# XC6SLX09-2FTG256C.net
KiCad netlist of a schematic drawn in Altium Designer
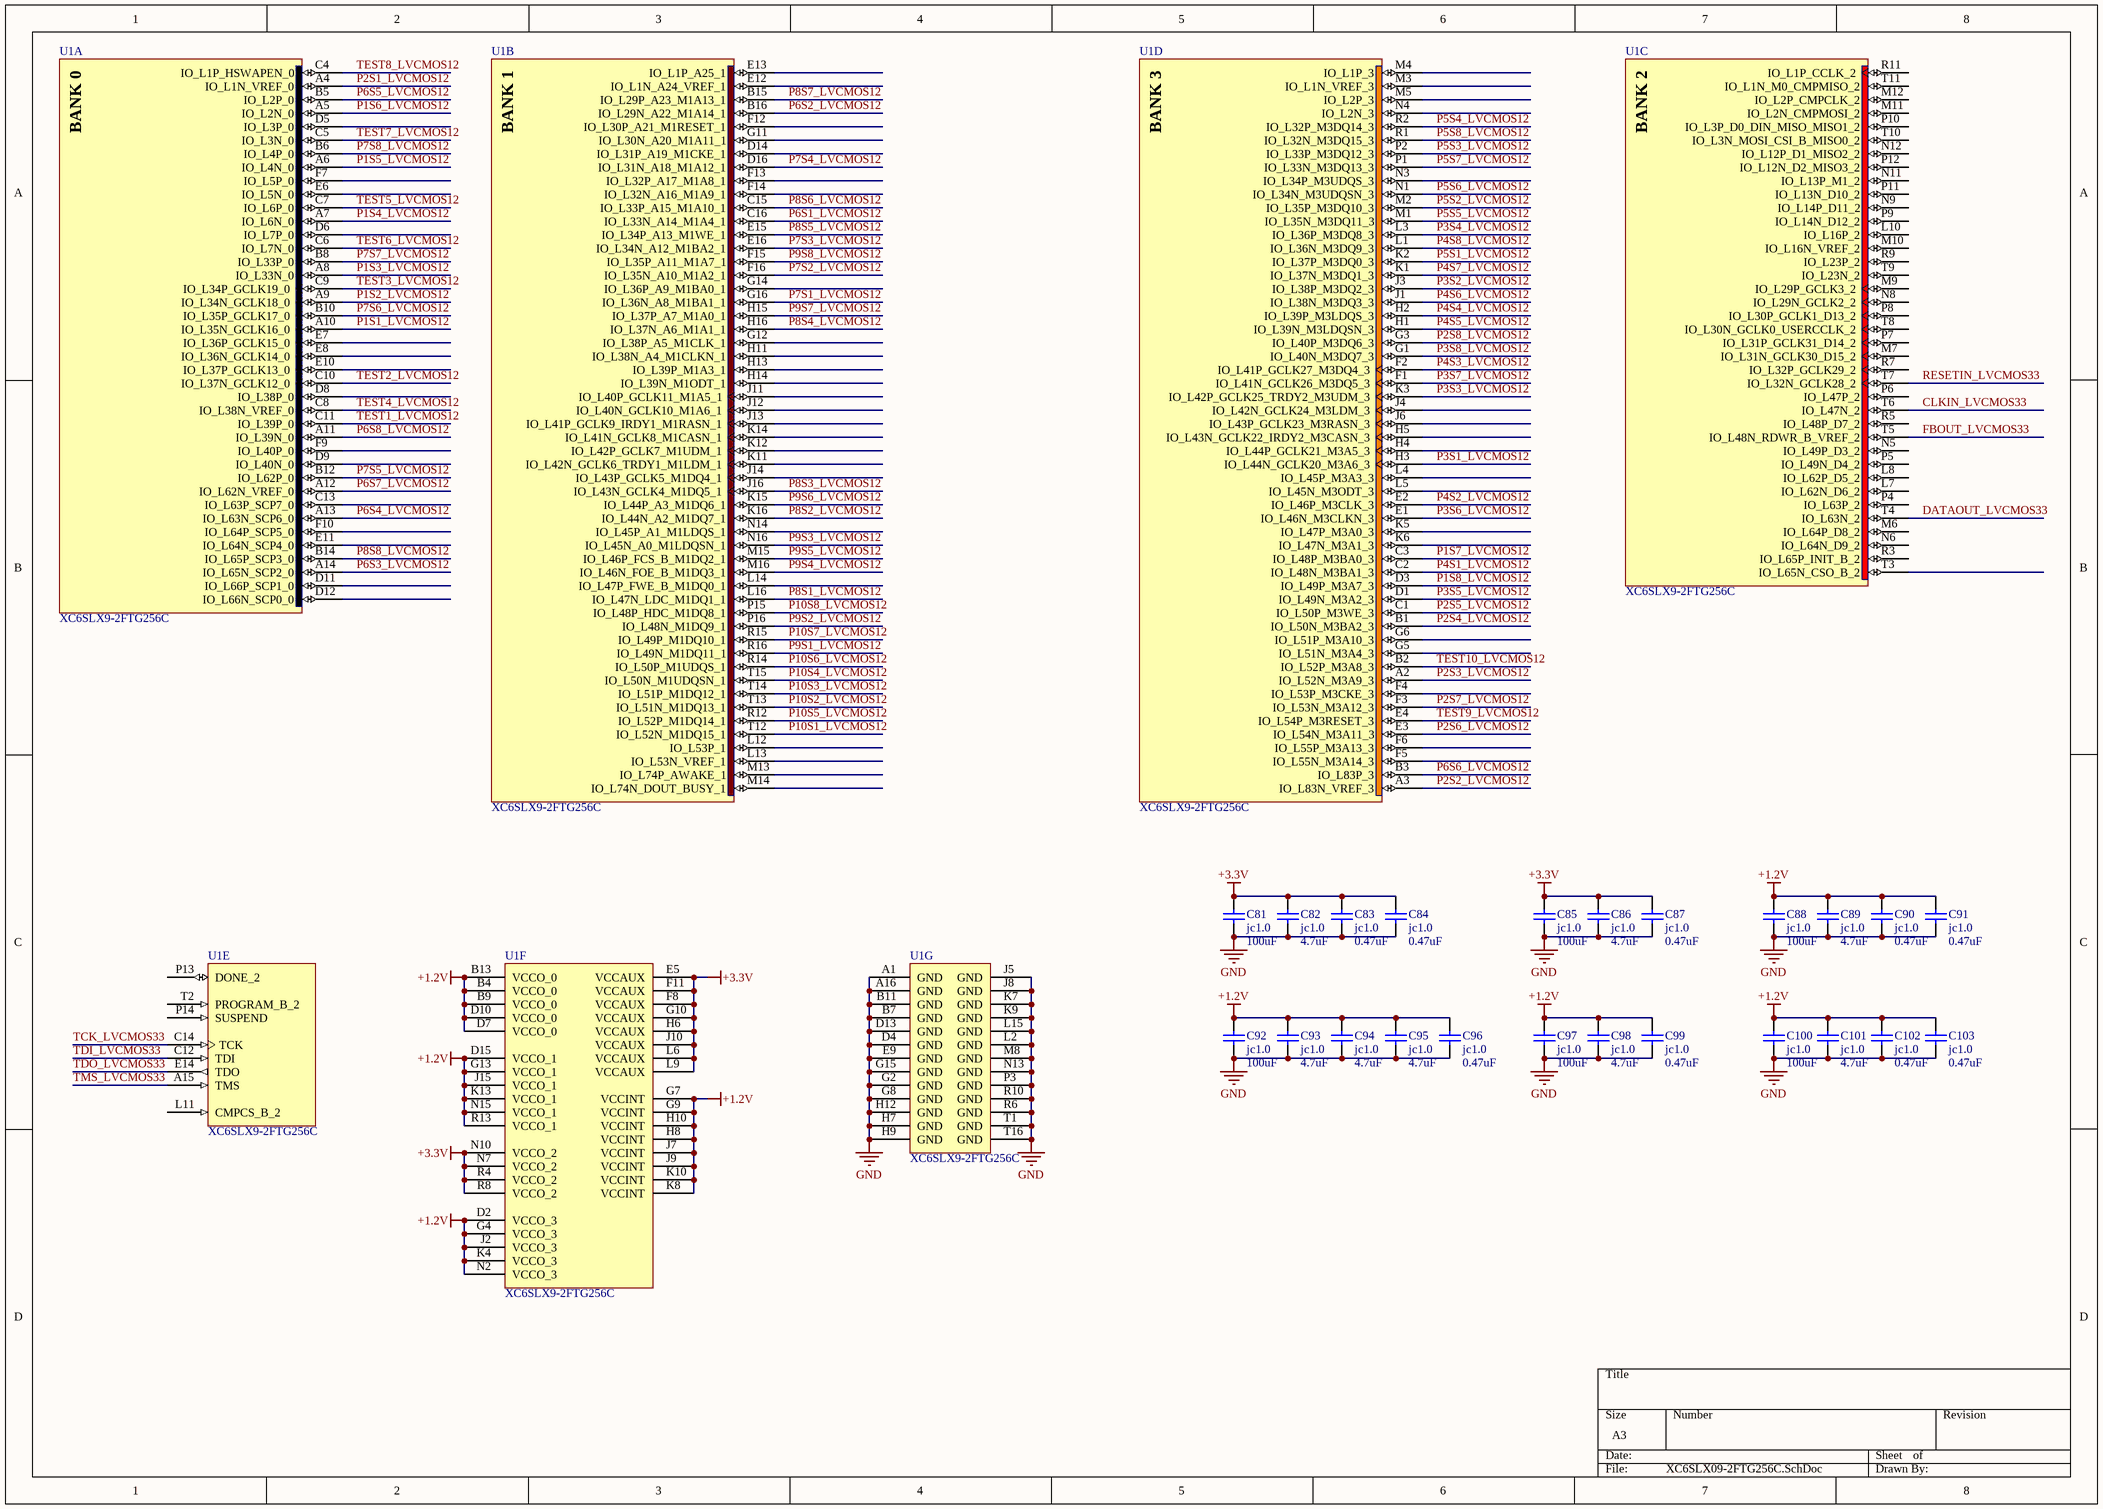
[diagram p0: XC6SLX09-2FTG256C.SchDoc]

(export (version "E")
  (design (tool "Eeschema 10.0.6"))
  (components
    (comp (ref "C81")
      (value "jc1.0")
      (footprint "0805")
      (description "Capacitor")
      (fields (field (name "ALTIUM_VALUE") "100uF") (field (name "PUBLISHER") "Altium Limited"))
      (libsource (lib "LIB01DXP2006SchLib") (part "Cap"))
    )
    (comp (ref "C82")
      (value "jc1.0")
      (footprint "0402")
      (description "Capacitor")
      (fields (field (name "ALTIUM_VALUE") "4.7uF") (field (name "PUBLISHER") "Altium Limited"))
      (libsource (lib "LIB01DXP2006SchLib") (part "Cap"))
    )
    (comp (ref "C83")
      (value "jc1.0")
      (footprint "0402")
      (description "Capacitor")
      (fields (field (name "ALTIUM_VALUE") "0.47uF") (field (name "PUBLISHER") "Altium Limited"))
      (libsource (lib "LIB01DXP2006SchLib") (part "Cap"))
    )
    (comp (ref "C84")
      (value "jc1.0")
      (footprint "0402")
      (description "Capacitor")
      (fields (field (name "ALTIUM_VALUE") "0.47uF") (field (name "PUBLISHER") "Altium Limited"))
      (libsource (lib "LIB01DXP2006SchLib") (part "Cap"))
    )
    (comp (ref "C85")
      (value "jc1.0")
      (footprint "0805")
      (description "Capacitor")
      (fields (field (name "ALTIUM_VALUE") "100uF") (field (name "PUBLISHER") "Altium Limited"))
      (libsource (lib "LIB01DXP2006SchLib") (part "Cap"))
    )
    (comp (ref "C86")
      (value "jc1.0")
      (footprint "0402")
      (description "Capacitor")
      (fields (field (name "ALTIUM_VALUE") "4.7uF") (field (name "PUBLISHER") "Altium Limited"))
      (libsource (lib "LIB01DXP2006SchLib") (part "Cap"))
    )
    (comp (ref "C87")
      (value "jc1.0")
      (footprint "0402")
      (description "Capacitor")
      (fields (field (name "ALTIUM_VALUE") "0.47uF") (field (name "PUBLISHER") "Altium Limited"))
      (libsource (lib "LIB01DXP2006SchLib") (part "Cap"))
    )
    (comp (ref "C88")
      (value "jc1.0")
      (footprint "0805")
      (description "Capacitor")
      (fields (field (name "ALTIUM_VALUE") "100uF") (field (name "PUBLISHER") "Altium Limited"))
      (libsource (lib "LIB01DXP2006SchLib") (part "Cap"))
    )
    (comp (ref "C89")
      (value "jc1.0")
      (footprint "0402")
      (description "Capacitor")
      (fields (field (name "ALTIUM_VALUE") "4.7uF") (field (name "PUBLISHER") "Altium Limited"))
      (libsource (lib "LIB01DXP2006SchLib") (part "Cap"))
    )
    (comp (ref "C90")
      (value "jc1.0")
      (footprint "0402")
      (description "Capacitor")
      (fields (field (name "ALTIUM_VALUE") "0.47uF") (field (name "PUBLISHER") "Altium Limited"))
      (libsource (lib "LIB01DXP2006SchLib") (part "Cap"))
    )
    (comp (ref "C91")
      (value "jc1.0")
      (footprint "0402")
      (description "Capacitor")
      (fields (field (name "ALTIUM_VALUE") "0.47uF") (field (name "PUBLISHER") "Altium Limited"))
      (libsource (lib "LIB01DXP2006SchLib") (part "Cap"))
    )
    (comp (ref "C92")
      (value "jc1.0")
      (footprint "0805")
      (description "Capacitor")
      (fields (field (name "ALTIUM_VALUE") "100uF") (field (name "PUBLISHER") "Altium Limited"))
      (libsource (lib "LIB01DXP2006SchLib") (part "Cap"))
    )
    (comp (ref "C93")
      (value "jc1.0")
      (footprint "0402")
      (description "Capacitor")
      (fields (field (name "ALTIUM_VALUE") "4.7uF") (field (name "PUBLISHER") "Altium Limited"))
      (libsource (lib "LIB01DXP2006SchLib") (part "Cap"))
    )
    (comp (ref "C94")
      (value "jc1.0")
      (footprint "0402")
      (description "Capacitor")
      (fields (field (name "ALTIUM_VALUE") "4.7uF") (field (name "PUBLISHER") "Altium Limited"))
      (libsource (lib "LIB01DXP2006SchLib") (part "Cap"))
    )
    (comp (ref "C95")
      (value "jc1.0")
      (footprint "0402")
      (description "Capacitor")
      (fields (field (name "ALTIUM_VALUE") "4.7uF") (field (name "PUBLISHER") "Altium Limited"))
      (libsource (lib "LIB01DXP2006SchLib") (part "Cap"))
    )
    (comp (ref "C96")
      (value "jc1.0")
      (footprint "0402")
      (description "Capacitor")
      (fields (field (name "ALTIUM_VALUE") "0.47uF") (field (name "PUBLISHER") "Altium Limited"))
      (libsource (lib "LIB01DXP2006SchLib") (part "Cap"))
    )
    (comp (ref "C97")
      (value "jc1.0")
      (footprint "0805")
      (description "Capacitor")
      (fields (field (name "ALTIUM_VALUE") "100uF") (field (name "PUBLISHER") "Altium Limited"))
      (libsource (lib "LIB01DXP2006SchLib") (part "Cap"))
    )
    (comp (ref "C98")
      (value "jc1.0")
      (footprint "0402")
      (description "Capacitor")
      (fields (field (name "ALTIUM_VALUE") "4.7uF") (field (name "PUBLISHER") "Altium Limited"))
      (libsource (lib "LIB01DXP2006SchLib") (part "Cap"))
    )
    (comp (ref "C99")
      (value "jc1.0")
      (footprint "0402")
      (description "Capacitor")
      (fields (field (name "ALTIUM_VALUE") "0.47uF") (field (name "PUBLISHER") "Altium Limited"))
      (libsource (lib "LIB01DXP2006SchLib") (part "Cap"))
    )
    (comp (ref "C100")
      (value "jc1.0")
      (footprint "0805")
      (description "Capacitor")
      (fields (field (name "ALTIUM_VALUE") "100uF") (field (name "PUBLISHER") "Altium Limited"))
      (libsource (lib "LIB01DXP2006SchLib") (part "Cap"))
    )
    (comp (ref "C101")
      (value "jc1.0")
      (footprint "0402")
      (description "Capacitor")
      (fields (field (name "ALTIUM_VALUE") "4.7uF") (field (name "PUBLISHER") "Altium Limited"))
      (libsource (lib "LIB01DXP2006SchLib") (part "Cap"))
    )
    (comp (ref "C102")
      (value "jc1.0")
      (footprint "0402")
      (description "Capacitor")
      (fields (field (name "ALTIUM_VALUE") "0.47uF") (field (name "PUBLISHER") "Altium Limited"))
      (libsource (lib "LIB01DXP2006SchLib") (part "Cap"))
    )
    (comp (ref "C103")
      (value "jc1.0")
      (footprint "0402")
      (description "Capacitor")
      (fields (field (name "ALTIUM_VALUE") "0.47uF") (field (name "PUBLISHER") "Altium Limited"))
      (libsource (lib "LIB01DXP2006SchLib") (part "Cap"))
    )
    (comp (ref "U1")
      (value "XC6SLX9-2FTG256C")
      (footprint "FTG256")
      (libsource (lib "Spartan-6") (part "XC6SLX9-2FTG256C"))
    )
  )
  (nets
    (net (code "1") (name "+1.2V") (class "Default")
      (node (ref "C100") (pin "2") (pinfunction "2_2") (pintype "passive"))
      (node (ref "C101") (pin "2") (pinfunction "2_2") (pintype "passive"))
      (node (ref "C102") (pin "2") (pinfunction "2_2") (pintype "passive"))
      (node (ref "C103") (pin "2") (pinfunction "2_2") (pintype "passive"))
      (node (ref "C88") (pin "2") (pinfunction "2_2") (pintype "passive"))
      (node (ref "C89") (pin "2") (pinfunction "2_2") (pintype "passive"))
      (node (ref "C90") (pin "2") (pinfunction "2_2") (pintype "passive"))
      (node (ref "C91") (pin "2") (pinfunction "2_2") (pintype "passive"))
      (node (ref "C92") (pin "2") (pinfunction "2_2") (pintype "passive"))
      (node (ref "C93") (pin "2") (pinfunction "2_2") (pintype "passive"))
      (node (ref "C94") (pin "2") (pinfunction "2_2") (pintype "passive"))
      (node (ref "C95") (pin "2") (pinfunction "2_2") (pintype "passive"))
      (node (ref "C96") (pin "2") (pinfunction "2_2") (pintype "passive"))
      (node (ref "C97") (pin "2") (pinfunction "2_2") (pintype "passive"))
      (node (ref "C98") (pin "2") (pinfunction "2_2") (pintype "passive"))
      (node (ref "C99") (pin "2") (pinfunction "2_2") (pintype "passive"))
      (node (ref "U1") (pin "B13") (pinfunction "VCCO_0_B13") (pintype "power_in"))
      (node (ref "U1") (pin "B4") (pinfunction "VCCO_0_B4") (pintype "power_in"))
      (node (ref "U1") (pin "B9") (pinfunction "VCCO_0_B9") (pintype "power_in"))
      (node (ref "U1") (pin "D10") (pinfunction "VCCO_0_D10") (pintype "power_in"))
      (node (ref "U1") (pin "D15") (pinfunction "VCCO_1_D15") (pintype "power_in"))
      (node (ref "U1") (pin "D2") (pinfunction "VCCO_3_D2") (pintype "power_in"))
      (node (ref "U1") (pin "D7") (pinfunction "VCCO_0_D7") (pintype "power_in"))
      (node (ref "U1") (pin "G13") (pinfunction "VCCO_1_G13") (pintype "power_in"))
      (node (ref "U1") (pin "G4") (pinfunction "VCCO_3_G4") (pintype "power_in"))
      (node (ref "U1") (pin "G7") (pinfunction "VCCINT_G7") (pintype "power_in"))
      (node (ref "U1") (pin "G9") (pinfunction "VCCINT_G9") (pintype "power_in"))
      (node (ref "U1") (pin "H10") (pinfunction "VCCINT_H10") (pintype "power_in"))
      (node (ref "U1") (pin "H8") (pinfunction "VCCINT_H8") (pintype "power_in"))
      (node (ref "U1") (pin "J15") (pinfunction "VCCO_1_J15") (pintype "power_in"))
      (node (ref "U1") (pin "J2") (pinfunction "VCCO_3_J2") (pintype "power_in"))
      (node (ref "U1") (pin "J7") (pinfunction "VCCINT_J7") (pintype "power_in"))
      (node (ref "U1") (pin "J9") (pinfunction "VCCINT_J9") (pintype "power_in"))
      (node (ref "U1") (pin "K10") (pinfunction "VCCINT_K10") (pintype "power_in"))
      (node (ref "U1") (pin "K13") (pinfunction "VCCO_1_K13") (pintype "power_in"))
      (node (ref "U1") (pin "K4") (pinfunction "VCCO_3_K4") (pintype "power_in"))
      (node (ref "U1") (pin "K8") (pinfunction "VCCINT_K8") (pintype "power_in"))
      (node (ref "U1") (pin "N15") (pinfunction "VCCO_1_N15") (pintype "power_in"))
      (node (ref "U1") (pin "N2") (pinfunction "VCCO_3_N2") (pintype "power_in"))
      (node (ref "U1") (pin "R13") (pinfunction "VCCO_1_R13") (pintype "power_in"))
    )
    (net (code "2") (name "+3.3V") (class "Default")
      (node (ref "C81") (pin "2") (pinfunction "2_2") (pintype "passive"))
      (node (ref "C82") (pin "2") (pinfunction "2_2") (pintype "passive"))
      (node (ref "C83") (pin "2") (pinfunction "2_2") (pintype "passive"))
      (node (ref "C84") (pin "2") (pinfunction "2_2") (pintype "passive"))
      (node (ref "C85") (pin "2") (pinfunction "2_2") (pintype "passive"))
      (node (ref "C86") (pin "2") (pinfunction "2_2") (pintype "passive"))
      (node (ref "C87") (pin "2") (pinfunction "2_2") (pintype "passive"))
      (node (ref "U1") (pin "E5") (pinfunction "VCCAUX_E5") (pintype "power_in"))
      (node (ref "U1") (pin "F11") (pinfunction "VCCAUX_F11") (pintype "power_in"))
      (node (ref "U1") (pin "F8") (pinfunction "VCCAUX_F8") (pintype "power_in"))
      (node (ref "U1") (pin "G10") (pinfunction "VCCAUX_G10") (pintype "power_in"))
      (node (ref "U1") (pin "H6") (pinfunction "VCCAUX_H6") (pintype "power_in"))
      (node (ref "U1") (pin "J10") (pinfunction "VCCAUX_J10") (pintype "power_in"))
      (node (ref "U1") (pin "L6") (pinfunction "VCCAUX_L6") (pintype "power_in"))
      (node (ref "U1") (pin "L9") (pinfunction "VCCAUX_L9") (pintype "power_in"))
      (node (ref "U1") (pin "N10") (pinfunction "VCCO_2_N10") (pintype "power_in"))
      (node (ref "U1") (pin "N7") (pinfunction "VCCO_2_N7") (pintype "power_in"))
      (node (ref "U1") (pin "R4") (pinfunction "VCCO_2_R4") (pintype "power_in"))
      (node (ref "U1") (pin "R8") (pinfunction "VCCO_2_R8") (pintype "power_in"))
    )
    (net (code "3") (name "/CLKIN_LVCMOS33") (class "Default")
      (node (ref "U1") (pin "T6") (pinfunction "IO_L47N_2_T6") (pintype "bidirectional"))
    )
    (net (code "4") (name "/DATAOUT_LVCMOS33") (class "Default")
      (node (ref "U1") (pin "T4") (pinfunction "IO_L63N_2_T4") (pintype "bidirectional"))
    )
    (net (code "5") (name "/FBOUT_LVCMOS33") (class "Default")
      (node (ref "U1") (pin "T5") (pinfunction "IO_L48N_RDWR_B_VREF_2_T5") (pintype "bidirectional"))
    )
    (net (code "6") (name "/P1S1_LVCMOS12") (class "Default")
      (node (ref "U1") (pin "A10") (pinfunction "IO_L35N_GCLK16_0_A10") (pintype "bidirectional"))
    )
    (net (code "7") (name "/P1S2_LVCMOS12") (class "Default")
      (node (ref "U1") (pin "A9") (pinfunction "IO_L34N_GCLK18_0_A9") (pintype "bidirectional"))
    )
    (net (code "8") (name "/P1S3_LVCMOS12") (class "Default")
      (node (ref "U1") (pin "A8") (pinfunction "IO_L33N_0_A8") (pintype "bidirectional"))
    )
    (net (code "9") (name "/P1S4_LVCMOS12") (class "Default")
      (node (ref "U1") (pin "A7") (pinfunction "IO_L6N_0_A7") (pintype "bidirectional"))
    )
    (net (code "10") (name "/P1S5_LVCMOS12") (class "Default")
      (node (ref "U1") (pin "A6") (pinfunction "IO_L4N_0_A6") (pintype "bidirectional"))
    )
    (net (code "11") (name "/P1S6_LVCMOS12") (class "Default")
      (node (ref "U1") (pin "A5") (pinfunction "IO_L2N_0_A5") (pintype "bidirectional"))
    )
    (net (code "12") (name "/P1S7_LVCMOS12") (class "Default")
      (node (ref "U1") (pin "C3") (pinfunction "IO_L48P_M3BA0_3_C3") (pintype "bidirectional"))
    )
    (net (code "13") (name "/P1S8_LVCMOS12") (class "Default")
      (node (ref "U1") (pin "D3") (pinfunction "IO_L49P_M3A7_3_D3") (pintype "bidirectional"))
    )
    (net (code "14") (name "/P2S1_LVCMOS12") (class "Default")
      (node (ref "U1") (pin "A4") (pinfunction "IO_L1N_VREF_0_A4") (pintype "bidirectional"))
    )
    (net (code "15") (name "/P2S2_LVCMOS12") (class "Default")
      (node (ref "U1") (pin "A3") (pinfunction "IO_L83N_VREF_3_A3") (pintype "bidirectional"))
    )
    (net (code "16") (name "/P2S3_LVCMOS12") (class "Default")
      (node (ref "U1") (pin "A2") (pinfunction "IO_L52N_M3A9_3_A2") (pintype "bidirectional"))
    )
    (net (code "17") (name "/P2S4_LVCMOS12") (class "Default")
      (node (ref "U1") (pin "B1") (pinfunction "IO_L50N_M3BA2_3_B1") (pintype "bidirectional"))
    )
    (net (code "18") (name "/P2S5_LVCMOS12") (class "Default")
      (node (ref "U1") (pin "C1") (pinfunction "IO_L50P_M3WE_3_C1") (pintype "bidirectional"))
    )
    (net (code "19") (name "/P2S6_LVCMOS12") (class "Default")
      (node (ref "U1") (pin "E3") (pinfunction "IO_L54N_M3A11_3_E3") (pintype "bidirectional"))
    )
    (net (code "20") (name "/P2S7_LVCMOS12") (class "Default")
      (node (ref "U1") (pin "F3") (pinfunction "IO_L53N_M3A12_3_F3") (pintype "bidirectional"))
    )
    (net (code "21") (name "/P2S8_LVCMOS12") (class "Default")
      (node (ref "U1") (pin "G3") (pinfunction "IO_L40P_M3DQ6_3_G3") (pintype "bidirectional"))
    )
    (net (code "22") (name "/P3S1_LVCMOS12") (class "Default")
      (node (ref "U1") (pin "H3") (pinfunction "IO_L44N_GCLK20_M3A6_3_H3") (pintype "bidirectional"))
    )
    (net (code "23") (name "/P3S2_LVCMOS12") (class "Default")
      (node (ref "U1") (pin "J3") (pinfunction "IO_L38P_M3DQ2_3_J3") (pintype "bidirectional"))
    )
    (net (code "24") (name "/P3S3_LVCMOS12") (class "Default")
      (node (ref "U1") (pin "K3") (pinfunction "IO_L42P_GCLK25_TRDY2_M3UDM_3_K3") (pintype "bidirectional"))
    )
    (net (code "25") (name "/P3S4_LVCMOS12") (class "Default")
      (node (ref "U1") (pin "L3") (pinfunction "IO_L36P_M3DQ8_3_L3") (pintype "bidirectional"))
    )
    (net (code "26") (name "/P3S5_LVCMOS12") (class "Default")
      (node (ref "U1") (pin "D1") (pinfunction "IO_L49N_M3A2_3_D1") (pintype "bidirectional"))
    )
    (net (code "27") (name "/P3S6_LVCMOS12") (class "Default")
      (node (ref "U1") (pin "E1") (pinfunction "IO_L46N_M3CLKN_3_E1") (pintype "bidirectional"))
    )
    (net (code "28") (name "/P3S7_LVCMOS12") (class "Default")
      (node (ref "U1") (pin "F1") (pinfunction "IO_L41N_GCLK26_M3DQ5_3_F1") (pintype "bidirectional"))
    )
    (net (code "29") (name "/P3S8_LVCMOS12") (class "Default")
      (node (ref "U1") (pin "G1") (pinfunction "IO_L40N_M3DQ7_3_G1") (pintype "bidirectional"))
    )
    (net (code "30") (name "/P4S1_LVCMOS12") (class "Default")
      (node (ref "U1") (pin "C2") (pinfunction "IO_L48N_M3BA1_3_C2") (pintype "bidirectional"))
    )
    (net (code "31") (name "/P4S2_LVCMOS12") (class "Default")
      (node (ref "U1") (pin "E2") (pinfunction "IO_L46P_M3CLK_3_E2") (pintype "bidirectional"))
    )
    (net (code "32") (name "/P4S3_LVCMOS12") (class "Default")
      (node (ref "U1") (pin "F2") (pinfunction "IO_L41P_GCLK27_M3DQ4_3_F2") (pintype "bidirectional"))
    )
    (net (code "33") (name "/P4S4_LVCMOS12") (class "Default")
      (node (ref "U1") (pin "H2") (pinfunction "IO_L39P_M3LDQS_3_H2") (pintype "bidirectional"))
    )
    (net (code "34") (name "/P4S5_LVCMOS12") (class "Default")
      (node (ref "U1") (pin "H1") (pinfunction "IO_L39N_M3LDQSN_3_H1") (pintype "bidirectional"))
    )
    (net (code "35") (name "/P4S6_LVCMOS12") (class "Default")
      (node (ref "U1") (pin "J1") (pinfunction "IO_L38N_M3DQ3_3_J1") (pintype "bidirectional"))
    )
    (net (code "36") (name "/P4S7_LVCMOS12") (class "Default")
      (node (ref "U1") (pin "K1") (pinfunction "IO_L37N_M3DQ1_3_K1") (pintype "bidirectional"))
    )
    (net (code "37") (name "/P4S8_LVCMOS12") (class "Default")
      (node (ref "U1") (pin "L1") (pinfunction "IO_L36N_M3DQ9_3_L1") (pintype "bidirectional"))
    )
    (net (code "38") (name "/P5S1_LVCMOS12") (class "Default")
      (node (ref "U1") (pin "K2") (pinfunction "IO_L37P_M3DQ0_3_K2") (pintype "bidirectional"))
    )
    (net (code "39") (name "/P5S2_LVCMOS12") (class "Default")
      (node (ref "U1") (pin "M2") (pinfunction "IO_L35P_M3DQ10_3_M2") (pintype "bidirectional"))
    )
    (net (code "40") (name "/P5S3_LVCMOS12") (class "Default")
      (node (ref "U1") (pin "P2") (pinfunction "IO_L33P_M3DQ12_3_P2") (pintype "bidirectional"))
    )
    (net (code "41") (name "/P5S4_LVCMOS12") (class "Default")
      (node (ref "U1") (pin "R2") (pinfunction "IO_L32P_M3DQ14_3_R2") (pintype "bidirectional"))
    )
    (net (code "42") (name "/P5S5_LVCMOS12") (class "Default")
      (node (ref "U1") (pin "M1") (pinfunction "IO_L35N_M3DQ11_3_M1") (pintype "bidirectional"))
    )
    (net (code "43") (name "/P5S6_LVCMOS12") (class "Default")
      (node (ref "U1") (pin "N1") (pinfunction "IO_L34N_M3UDQSN_3_N1") (pintype "bidirectional"))
    )
    (net (code "44") (name "/P5S7_LVCMOS12") (class "Default")
      (node (ref "U1") (pin "P1") (pinfunction "IO_L33N_M3DQ13_3_P1") (pintype "bidirectional"))
    )
    (net (code "45") (name "/P5S8_LVCMOS12") (class "Default")
      (node (ref "U1") (pin "R1") (pinfunction "IO_L32N_M3DQ15_3_R1") (pintype "bidirectional"))
    )
    (net (code "46") (name "/P6S1_LVCMOS12") (class "Default")
      (node (ref "U1") (pin "C16") (pinfunction "IO_L33N_A14_M1A4_1_C16") (pintype "bidirectional"))
    )
    (net (code "47") (name "/P6S2_LVCMOS12") (class "Default")
      (node (ref "U1") (pin "B16") (pinfunction "IO_L29N_A22_M1A14_1_B16") (pintype "bidirectional"))
    )
    (net (code "48") (name "/P6S3_LVCMOS12") (class "Default")
      (node (ref "U1") (pin "A14") (pinfunction "IO_L65N_SCP2_0_A14") (pintype "bidirectional"))
    )
    (net (code "49") (name "/P6S4_LVCMOS12") (class "Default")
      (node (ref "U1") (pin "A13") (pinfunction "IO_L63N_SCP6_0_A13") (pintype "bidirectional"))
    )
    (net (code "50") (name "/P6S5_LVCMOS12") (class "Default")
      (node (ref "U1") (pin "B5") (pinfunction "IO_L2P_0_B5") (pintype "bidirectional"))
    )
    (net (code "51") (name "/P6S6_LVCMOS12") (class "Default")
      (node (ref "U1") (pin "B3") (pinfunction "IO_L83P_3_B3") (pintype "bidirectional"))
    )
    (net (code "52") (name "/P6S7_LVCMOS12") (class "Default")
      (node (ref "U1") (pin "A12") (pinfunction "IO_L62N_VREF_0_A12") (pintype "bidirectional"))
    )
    (net (code "53") (name "/P6S8_LVCMOS12") (class "Default")
      (node (ref "U1") (pin "A11") (pinfunction "IO_L39N_0_A11") (pintype "bidirectional"))
    )
    (net (code "54") (name "/P7S1_LVCMOS12") (class "Default")
      (node (ref "U1") (pin "G16") (pinfunction "IO_L36N_A8_M1BA1_1_G16") (pintype "bidirectional"))
    )
    (net (code "55") (name "/P7S2_LVCMOS12") (class "Default")
      (node (ref "U1") (pin "F16") (pinfunction "IO_L35N_A10_M1A2_1_F16") (pintype "bidirectional"))
    )
    (net (code "56") (name "/P7S3_LVCMOS12") (class "Default")
      (node (ref "U1") (pin "E16") (pinfunction "IO_L34N_A12_M1BA2_1_E16") (pintype "bidirectional"))
    )
    (net (code "57") (name "/P7S4_LVCMOS12") (class "Default")
      (node (ref "U1") (pin "D16") (pinfunction "IO_L31N_A18_M1A12_1_D16") (pintype "bidirectional"))
    )
    (net (code "58") (name "/P7S5_LVCMOS12") (class "Default")
      (node (ref "U1") (pin "B12") (pinfunction "IO_L62P_0_B12") (pintype "bidirectional"))
    )
    (net (code "59") (name "/P7S6_LVCMOS12") (class "Default")
      (node (ref "U1") (pin "B10") (pinfunction "IO_L35P_GCLK17_0_B10") (pintype "bidirectional"))
    )
    (net (code "60") (name "/P7S7_LVCMOS12") (class "Default")
      (node (ref "U1") (pin "B8") (pinfunction "IO_L33P_0_B8") (pintype "bidirectional"))
    )
    (net (code "61") (name "/P7S8_LVCMOS12") (class "Default")
      (node (ref "U1") (pin "B6") (pinfunction "IO_L4P_0_B6") (pintype "bidirectional"))
    )
    (net (code "62") (name "/P8S1_LVCMOS12") (class "Default")
      (node (ref "U1") (pin "L16") (pinfunction "IO_L47N_LDC_M1DQ1_1_L16") (pintype "bidirectional"))
    )
    (net (code "63") (name "/P8S2_LVCMOS12") (class "Default")
      (node (ref "U1") (pin "K16") (pinfunction "IO_L44N_A2_M1DQ7_1_K16") (pintype "bidirectional"))
    )
    (net (code "64") (name "/P8S3_LVCMOS12") (class "Default")
      (node (ref "U1") (pin "J16") (pinfunction "IO_L43N_GCLK4_M1DQ5_1_J16") (pintype "bidirectional"))
    )
    (net (code "65") (name "/P8S4_LVCMOS12") (class "Default")
      (node (ref "U1") (pin "H16") (pinfunction "IO_L37N_A6_M1A1_1_H16") (pintype "bidirectional"))
    )
    (net (code "66") (name "/P8S5_LVCMOS12") (class "Default")
      (node (ref "U1") (pin "E15") (pinfunction "IO_L34P_A13_M1WE_1_E15") (pintype "bidirectional"))
    )
    (net (code "67") (name "/P8S6_LVCMOS12") (class "Default")
      (node (ref "U1") (pin "C15") (pinfunction "IO_L33P_A15_M1A10_1_C15") (pintype "bidirectional"))
    )
    (net (code "68") (name "/P8S7_LVCMOS12") (class "Default")
      (node (ref "U1") (pin "B15") (pinfunction "IO_L29P_A23_M1A13_1_B15") (pintype "bidirectional"))
    )
    (net (code "69") (name "/P8S8_LVCMOS12") (class "Default")
      (node (ref "U1") (pin "B14") (pinfunction "IO_L65P_SCP3_0_B14") (pintype "bidirectional"))
    )
    (net (code "70") (name "/P9S1_LVCMOS12") (class "Default")
      (node (ref "U1") (pin "R16") (pinfunction "IO_L49N_M1DQ11_1_R16") (pintype "bidirectional"))
    )
    (net (code "71") (name "/P9S2_LVCMOS12") (class "Default")
      (node (ref "U1") (pin "P16") (pinfunction "IO_L48N_M1DQ9_1_P16") (pintype "bidirectional"))
    )
    (net (code "72") (name "/P9S3_LVCMOS12") (class "Default")
      (node (ref "U1") (pin "N16") (pinfunction "IO_L45N_A0_M1LDQSN_1_N16") (pintype "bidirectional"))
    )
    (net (code "73") (name "/P9S4_LVCMOS12") (class "Default")
      (node (ref "U1") (pin "M16") (pinfunction "IO_L46N_FOE_B_M1DQ3_1_M16") (pintype "bidirectional"))
    )
    (net (code "74") (name "/P9S5_LVCMOS12") (class "Default")
      (node (ref "U1") (pin "M15") (pinfunction "IO_L46P_FCS_B_M1DQ2_1_M15") (pintype "bidirectional"))
    )
    (net (code "75") (name "/P9S6_LVCMOS12") (class "Default")
      (node (ref "U1") (pin "K15") (pinfunction "IO_L44P_A3_M1DQ6_1_K15") (pintype "bidirectional"))
    )
    (net (code "76") (name "/P9S7_LVCMOS12") (class "Default")
      (node (ref "U1") (pin "H15") (pinfunction "IO_L37P_A7_M1A0_1_H15") (pintype "bidirectional"))
    )
    (net (code "77") (name "/P9S8_LVCMOS12") (class "Default")
      (node (ref "U1") (pin "F15") (pinfunction "IO_L35P_A11_M1A7_1_F15") (pintype "bidirectional"))
    )
    (net (code "78") (name "/P10S1_LVCMOS12") (class "Default")
      (node (ref "U1") (pin "T12") (pinfunction "IO_L52N_M1DQ15_1_T12") (pintype "bidirectional"))
    )
    (net (code "79") (name "/P10S2_LVCMOS12") (class "Default")
      (node (ref "U1") (pin "T13") (pinfunction "IO_L51N_M1DQ13_1_T13") (pintype "bidirectional"))
    )
    (net (code "80") (name "/P10S3_LVCMOS12") (class "Default")
      (node (ref "U1") (pin "T14") (pinfunction "IO_L51P_M1DQ12_1_T14") (pintype "bidirectional"))
    )
    (net (code "81") (name "/P10S4_LVCMOS12") (class "Default")
      (node (ref "U1") (pin "T15") (pinfunction "IO_L50N_M1UDQSN_1_T15") (pintype "bidirectional"))
    )
    (net (code "82") (name "/P10S5_LVCMOS12") (class "Default")
      (node (ref "U1") (pin "R12") (pinfunction "IO_L52P_M1DQ14_1_R12") (pintype "bidirectional"))
    )
    (net (code "83") (name "/P10S6_LVCMOS12") (class "Default")
      (node (ref "U1") (pin "R14") (pinfunction "IO_L50P_M1UDQS_1_R14") (pintype "bidirectional"))
    )
    (net (code "84") (name "/P10S7_LVCMOS12") (class "Default")
      (node (ref "U1") (pin "R15") (pinfunction "IO_L49P_M1DQ10_1_R15") (pintype "bidirectional"))
    )
    (net (code "85") (name "/P10S8_LVCMOS12") (class "Default")
      (node (ref "U1") (pin "P15") (pinfunction "IO_L48P_HDC_M1DQ8_1_P15") (pintype "bidirectional"))
    )
    (net (code "86") (name "/RESETIN_LVCMOS33") (class "Default")
      (node (ref "U1") (pin "T7") (pinfunction "IO_L32N_GCLK28_2_T7") (pintype "bidirectional"))
    )
    (net (code "87") (name "/TCK_LVCMOS33") (class "Default")
      (node (ref "U1") (pin "C14") (pinfunction "TCK_C14") (pintype "input"))
    )
    (net (code "88") (name "/TDI_LVCMOS33") (class "Default")
      (node (ref "U1") (pin "C12") (pinfunction "TDI_C12") (pintype "input"))
    )
    (net (code "89") (name "/TDO_LVCMOS33") (class "Default")
      (node (ref "U1") (pin "E14") (pinfunction "TDO_E14") (pintype "output"))
    )
    (net (code "90") (name "/TEST1_LVCMOS12") (class "Default")
      (node (ref "U1") (pin "C11") (pinfunction "IO_L39P_0_C11") (pintype "bidirectional"))
    )
    (net (code "91") (name "/TEST2_LVCMOS12") (class "Default")
      (node (ref "U1") (pin "C10") (pinfunction "IO_L37N_GCLK12_0_C10") (pintype "bidirectional"))
    )
    (net (code "92") (name "/TEST3_LVCMOS12") (class "Default")
      (node (ref "U1") (pin "C9") (pinfunction "IO_L34P_GCLK19_0_C9") (pintype "bidirectional"))
    )
    (net (code "93") (name "/TEST4_LVCMOS12") (class "Default")
      (node (ref "U1") (pin "C8") (pinfunction "IO_L38N_VREF_0_C8") (pintype "bidirectional"))
    )
    (net (code "94") (name "/TEST5_LVCMOS12") (class "Default")
      (node (ref "U1") (pin "C7") (pinfunction "IO_L6P_0_C7") (pintype "bidirectional"))
    )
    (net (code "95") (name "/TEST6_LVCMOS12") (class "Default")
      (node (ref "U1") (pin "C6") (pinfunction "IO_L7N_0_C6") (pintype "bidirectional"))
    )
    (net (code "96") (name "/TEST7_LVCMOS12") (class "Default")
      (node (ref "U1") (pin "C5") (pinfunction "IO_L3N_0_C5") (pintype "bidirectional"))
    )
    (net (code "97") (name "/TEST8_LVCMOS12") (class "Default")
      (node (ref "U1") (pin "C4") (pinfunction "IO_L1P_HSWAPEN_0_C4") (pintype "bidirectional"))
    )
    (net (code "98") (name "/TEST9_LVCMOS12") (class "Default")
      (node (ref "U1") (pin "E4") (pinfunction "IO_L54P_M3RESET_3_E4") (pintype "bidirectional"))
    )
    (net (code "99") (name "/TEST10_LVCMOS12") (class "Default")
      (node (ref "U1") (pin "B2") (pinfunction "IO_L52P_M3A8_3_B2") (pintype "bidirectional"))
    )
    (net (code "100") (name "/TMS_LVCMOS33") (class "Default")
      (node (ref "U1") (pin "A15") (pinfunction "TMS_A15") (pintype "input"))
    )
    (net (code "101") (name "GND") (class "Default")
      (node (ref "C100") (pin "1") (pinfunction "1_1") (pintype "passive"))
      (node (ref "C101") (pin "1") (pinfunction "1_1") (pintype "passive"))
      (node (ref "C102") (pin "1") (pinfunction "1_1") (pintype "passive"))
      (node (ref "C103") (pin "1") (pinfunction "1_1") (pintype "passive"))
      (node (ref "C81") (pin "1") (pinfunction "1_1") (pintype "passive"))
      (node (ref "C82") (pin "1") (pinfunction "1_1") (pintype "passive"))
      (node (ref "C83") (pin "1") (pinfunction "1_1") (pintype "passive"))
      (node (ref "C84") (pin "1") (pinfunction "1_1") (pintype "passive"))
      (node (ref "C85") (pin "1") (pinfunction "1_1") (pintype "passive"))
      (node (ref "C86") (pin "1") (pinfunction "1_1") (pintype "passive"))
      (node (ref "C87") (pin "1") (pinfunction "1_1") (pintype "passive"))
      (node (ref "C88") (pin "1") (pinfunction "1_1") (pintype "passive"))
      (node (ref "C89") (pin "1") (pinfunction "1_1") (pintype "passive"))
      (node (ref "C90") (pin "1") (pinfunction "1_1") (pintype "passive"))
      (node (ref "C91") (pin "1") (pinfunction "1_1") (pintype "passive"))
      (node (ref "C92") (pin "1") (pinfunction "1_1") (pintype "passive"))
      (node (ref "C93") (pin "1") (pinfunction "1_1") (pintype "passive"))
      (node (ref "C94") (pin "1") (pinfunction "1_1") (pintype "passive"))
      (node (ref "C95") (pin "1") (pinfunction "1_1") (pintype "passive"))
      (node (ref "C96") (pin "1") (pinfunction "1_1") (pintype "passive"))
      (node (ref "C97") (pin "1") (pinfunction "1_1") (pintype "passive"))
      (node (ref "C98") (pin "1") (pinfunction "1_1") (pintype "passive"))
      (node (ref "C99") (pin "1") (pinfunction "1_1") (pintype "passive"))
      (node (ref "U1") (pin "A1") (pinfunction "GND_A1") (pintype "power_in"))
      (node (ref "U1") (pin "A16") (pinfunction "GND_A16") (pintype "power_in"))
      (node (ref "U1") (pin "B11") (pinfunction "GND_B11") (pintype "power_in"))
      (node (ref "U1") (pin "B7") (pinfunction "GND_B7") (pintype "power_in"))
      (node (ref "U1") (pin "D13") (pinfunction "GND_D13") (pintype "power_in"))
      (node (ref "U1") (pin "D4") (pinfunction "GND_D4") (pintype "power_in"))
      (node (ref "U1") (pin "E9") (pinfunction "GND_E9") (pintype "power_in"))
      (node (ref "U1") (pin "G15") (pinfunction "GND_G15") (pintype "power_in"))
      (node (ref "U1") (pin "G2") (pinfunction "GND_G2") (pintype "power_in"))
      (node (ref "U1") (pin "G8") (pinfunction "GND_G8") (pintype "power_in"))
      (node (ref "U1") (pin "H12") (pinfunction "GND_H12") (pintype "power_in"))
      (node (ref "U1") (pin "H7") (pinfunction "GND_H7") (pintype "power_in"))
      (node (ref "U1") (pin "H9") (pinfunction "GND_H9") (pintype "power_in"))
      (node (ref "U1") (pin "J5") (pinfunction "GND_J5") (pintype "power_in"))
      (node (ref "U1") (pin "J8") (pinfunction "GND_J8") (pintype "power_in"))
      (node (ref "U1") (pin "K7") (pinfunction "GND_K7") (pintype "power_in"))
      (node (ref "U1") (pin "K9") (pinfunction "GND_K9") (pintype "power_in"))
      (node (ref "U1") (pin "L15") (pinfunction "GND_L15") (pintype "power_in"))
      (node (ref "U1") (pin "L2") (pinfunction "GND_L2") (pintype "power_in"))
      (node (ref "U1") (pin "M8") (pinfunction "GND_M8") (pintype "power_in"))
      (node (ref "U1") (pin "N13") (pinfunction "GND_N13") (pintype "power_in"))
      (node (ref "U1") (pin "P3") (pinfunction "GND_P3") (pintype "power_in"))
      (node (ref "U1") (pin "R10") (pinfunction "GND_R10") (pintype "power_in"))
      (node (ref "U1") (pin "R6") (pinfunction "GND_R6") (pintype "power_in"))
      (node (ref "U1") (pin "T1") (pinfunction "GND_T1") (pintype "power_in"))
      (node (ref "U1") (pin "T16") (pinfunction "GND_T16") (pintype "power_in"))
    )
    (net (code "102") (name "unconnected-(U1A-IO_L3P_0-PadD5)") (class "Default")
      (node (ref "U1") (pin "D5") (pinfunction "IO_L3P_0_D5") (pintype "bidirectional"))
    )
    (net (code "103") (name "unconnected-(U1A-IO_L5N_0-PadE6)") (class "Default")
      (node (ref "U1") (pin "E6") (pinfunction "IO_L5N_0_E6") (pintype "bidirectional"))
    )
    (net (code "104") (name "unconnected-(U1A-IO_L5P_0-PadF7)") (class "Default")
      (node (ref "U1") (pin "F7") (pinfunction "IO_L5P_0_F7") (pintype "bidirectional"))
    )
    (net (code "105") (name "unconnected-(U1A-IO_L7P_0-PadD6)") (class "Default")
      (node (ref "U1") (pin "D6") (pinfunction "IO_L7P_0_D6") (pintype "bidirectional"))
    )
    (net (code "106") (name "unconnected-(U1A-IO_L36N_GCLK14_0-PadE8)") (class "Default")
      (node (ref "U1") (pin "E8") (pinfunction "IO_L36N_GCLK14_0_E8") (pintype "bidirectional"))
    )
    (net (code "107") (name "unconnected-(U1A-IO_L36P_GCLK15_0-PadE7)") (class "Default")
      (node (ref "U1") (pin "E7") (pinfunction "IO_L36P_GCLK15_0_E7") (pintype "bidirectional"))
    )
    (net (code "108") (name "unconnected-(U1A-IO_L37P_GCLK13_0-PadE10)") (class "Default")
      (node (ref "U1") (pin "E10") (pinfunction "IO_L37P_GCLK13_0_E10") (pintype "bidirectional"))
    )
    (net (code "109") (name "unconnected-(U1A-IO_L38P_0-PadD8)") (class "Default")
      (node (ref "U1") (pin "D8") (pinfunction "IO_L38P_0_D8") (pintype "bidirectional"))
    )
    (net (code "110") (name "unconnected-(U1A-IO_L40N_0-PadD9)") (class "Default")
      (node (ref "U1") (pin "D9") (pinfunction "IO_L40N_0_D9") (pintype "bidirectional"))
    )
    (net (code "111") (name "unconnected-(U1A-IO_L40P_0-PadF9)") (class "Default")
      (node (ref "U1") (pin "F9") (pinfunction "IO_L40P_0_F9") (pintype "bidirectional"))
    )
    (net (code "112") (name "unconnected-(U1A-IO_L63P_SCP7_0-PadC13)") (class "Default")
      (node (ref "U1") (pin "C13") (pinfunction "IO_L63P_SCP7_0_C13") (pintype "bidirectional"))
    )
    (net (code "113") (name "unconnected-(U1A-IO_L64N_SCP4_0-PadE11)") (class "Default")
      (node (ref "U1") (pin "E11") (pinfunction "IO_L64N_SCP4_0_E11") (pintype "bidirectional"))
    )
    (net (code "114") (name "unconnected-(U1A-IO_L64P_SCP5_0-PadF10)") (class "Default")
      (node (ref "U1") (pin "F10") (pinfunction "IO_L64P_SCP5_0_F10") (pintype "bidirectional"))
    )
    (net (code "115") (name "unconnected-(U1A-IO_L66N_SCP0_0-PadD12)") (class "Default")
      (node (ref "U1") (pin "D12") (pinfunction "IO_L66N_SCP0_0_D12") (pintype "bidirectional"))
    )
    (net (code "116") (name "unconnected-(U1A-IO_L66P_SCP1_0-PadD11)") (class "Default")
      (node (ref "U1") (pin "D11") (pinfunction "IO_L66P_SCP1_0_D11") (pintype "bidirectional"))
    )
    (net (code "117") (name "unconnected-(U1B-IO_L1N_A24_VREF_1-PadE12)") (class "Default")
      (node (ref "U1") (pin "E12") (pinfunction "IO_L1N_A24_VREF_1_E12") (pintype "bidirectional"))
    )
    (net (code "118") (name "unconnected-(U1B-IO_L1P_A25_1-PadE13)") (class "Default")
      (node (ref "U1") (pin "E13") (pinfunction "IO_L1P_A25_1_E13") (pintype "bidirectional"))
    )
    (net (code "119") (name "unconnected-(U1B-IO_L30N_A20_M1A11_1-PadG11)") (class "Default")
      (node (ref "U1") (pin "G11") (pinfunction "IO_L30N_A20_M1A11_1_G11") (pintype "bidirectional"))
    )
    (net (code "120") (name "unconnected-(U1B-IO_L30P_A21_M1RESET_1-PadF12)") (class "Default")
      (node (ref "U1") (pin "F12") (pinfunction "IO_L30P_A21_M1RESET_1_F12") (pintype "bidirectional"))
    )
    (net (code "121") (name "unconnected-(U1B-IO_L31P_A19_M1CKE_1-PadD14)") (class "Default")
      (node (ref "U1") (pin "D14") (pinfunction "IO_L31P_A19_M1CKE_1_D14") (pintype "bidirectional"))
    )
    (net (code "122") (name "unconnected-(U1B-IO_L32N_A16_M1A9_1-PadF14)") (class "Default")
      (node (ref "U1") (pin "F14") (pinfunction "IO_L32N_A16_M1A9_1_F14") (pintype "bidirectional"))
    )
    (net (code "123") (name "unconnected-(U1B-IO_L32P_A17_M1A8_1-PadF13)") (class "Default")
      (node (ref "U1") (pin "F13") (pinfunction "IO_L32P_A17_M1A8_1_F13") (pintype "bidirectional"))
    )
    (net (code "124") (name "unconnected-(U1B-IO_L36P_A9_M1BA0_1-PadG14)") (class "Default")
      (node (ref "U1") (pin "G14") (pinfunction "IO_L36P_A9_M1BA0_1_G14") (pintype "bidirectional"))
    )
    (net (code "125") (name "unconnected-(U1B-IO_L38N_A4_M1CLKN_1-PadH11)") (class "Default")
      (node (ref "U1") (pin "H11") (pinfunction "IO_L38N_A4_M1CLKN_1_H11") (pintype "bidirectional"))
    )
    (net (code "126") (name "unconnected-(U1B-IO_L38P_A5_M1CLK_1-PadG12)") (class "Default")
      (node (ref "U1") (pin "G12") (pinfunction "IO_L38P_A5_M1CLK_1_G12") (pintype "bidirectional"))
    )
    (net (code "127") (name "unconnected-(U1B-IO_L39N_M1ODT_1-PadH14)") (class "Default")
      (node (ref "U1") (pin "H14") (pinfunction "IO_L39N_M1ODT_1_H14") (pintype "bidirectional"))
    )
    (net (code "128") (name "unconnected-(U1B-IO_L39P_M1A3_1-PadH13)") (class "Default")
      (node (ref "U1") (pin "H13") (pinfunction "IO_L39P_M1A3_1_H13") (pintype "bidirectional"))
    )
    (net (code "129") (name "unconnected-(U1B-IO_L40N_GCLK10_M1A6_1-PadJ12)") (class "Default")
      (node (ref "U1") (pin "J12") (pinfunction "IO_L40N_GCLK10_M1A6_1_J12") (pintype "bidirectional"))
    )
    (net (code "130") (name "unconnected-(U1B-IO_L40P_GCLK11_M1A5_1-PadJ11)") (class "Default")
      (node (ref "U1") (pin "J11") (pinfunction "IO_L40P_GCLK11_M1A5_1_J11") (pintype "bidirectional"))
    )
    (net (code "131") (name "unconnected-(U1B-IO_L41N_GCLK8_M1CASN_1-PadK14)") (class "Default")
      (node (ref "U1") (pin "K14") (pinfunction "IO_L41N_GCLK8_M1CASN_1_K14") (pintype "bidirectional"))
    )
    (net (code "132") (name "unconnected-(U1B-IO_L41P_GCLK9_IRDY1_M1RASN_1-PadJ13)") (class "Default")
      (node (ref "U1") (pin "J13") (pinfunction "IO_L41P_GCLK9_IRDY1_M1RASN_1_J13") (pintype "bidirectional"))
    )
    (net (code "133") (name "unconnected-(U1B-IO_L42N_GCLK6_TRDY1_M1LDM_1-PadK11)") (class "Default")
      (node (ref "U1") (pin "K11") (pinfunction "IO_L42N_GCLK6_TRDY1_M1LDM_1_K11") (pintype "bidirectional"))
    )
    (net (code "134") (name "unconnected-(U1B-IO_L42P_GCLK7_M1UDM_1-PadK12)") (class "Default")
      (node (ref "U1") (pin "K12") (pinfunction "IO_L42P_GCLK7_M1UDM_1_K12") (pintype "bidirectional"))
    )
    (net (code "135") (name "unconnected-(U1B-IO_L43P_GCLK5_M1DQ4_1-PadJ14)") (class "Default")
      (node (ref "U1") (pin "J14") (pinfunction "IO_L43P_GCLK5_M1DQ4_1_J14") (pintype "bidirectional"))
    )
    (net (code "136") (name "unconnected-(U1B-IO_L45P_A1_M1LDQS_1-PadN14)") (class "Default")
      (node (ref "U1") (pin "N14") (pinfunction "IO_L45P_A1_M1LDQS_1_N14") (pintype "bidirectional"))
    )
    (net (code "137") (name "unconnected-(U1B-IO_L47P_FWE_B_M1DQ0_1-PadL14)") (class "Default")
      (node (ref "U1") (pin "L14") (pinfunction "IO_L47P_FWE_B_M1DQ0_1_L14") (pintype "bidirectional"))
    )
    (net (code "138") (name "unconnected-(U1B-IO_L53N_VREF_1-PadL13)") (class "Default")
      (node (ref "U1") (pin "L13") (pinfunction "IO_L53N_VREF_1_L13") (pintype "bidirectional"))
    )
    (net (code "139") (name "unconnected-(U1B-IO_L53P_1-PadL12)") (class "Default")
      (node (ref "U1") (pin "L12") (pinfunction "IO_L53P_1_L12") (pintype "bidirectional"))
    )
    (net (code "140") (name "unconnected-(U1B-IO_L74N_DOUT_BUSY_1-PadM14)") (class "Default")
      (node (ref "U1") (pin "M14") (pinfunction "IO_L74N_DOUT_BUSY_1_M14") (pintype "bidirectional"))
    )
    (net (code "141") (name "unconnected-(U1B-IO_L74P_AWAKE_1-PadM13)") (class "Default")
      (node (ref "U1") (pin "M13") (pinfunction "IO_L74P_AWAKE_1_M13") (pintype "bidirectional"))
    )
    (net (code "142") (name "unconnected-(U1C-IO_L1N_M0_CMPMISO_2-PadT11)") (class "Default")
      (node (ref "U1") (pin "T11") (pinfunction "IO_L1N_M0_CMPMISO_2_T11") (pintype "bidirectional"))
    )
    (net (code "143") (name "unconnected-(U1C-IO_L1P_CCLK_2-PadR11)") (class "Default")
      (node (ref "U1") (pin "R11") (pinfunction "IO_L1P_CCLK_2_R11") (pintype "bidirectional"))
    )
    (net (code "144") (name "unconnected-(U1C-IO_L2N_CMPMOSI_2-PadM11)") (class "Default")
      (node (ref "U1") (pin "M11") (pinfunction "IO_L2N_CMPMOSI_2_M11") (pintype "bidirectional"))
    )
    (net (code "145") (name "unconnected-(U1C-IO_L2P_CMPCLK_2-PadM12)") (class "Default")
      (node (ref "U1") (pin "M12") (pinfunction "IO_L2P_CMPCLK_2_M12") (pintype "bidirectional"))
    )
    (net (code "146") (name "unconnected-(U1C-IO_L3N_MOSI_CSI_B_MISO0_2-PadT10)") (class "Default")
      (node (ref "U1") (pin "T10") (pinfunction "IO_L3N_MOSI_CSI_B_MISO0_2_T10") (pintype "bidirectional"))
    )
    (net (code "147") (name "unconnected-(U1C-IO_L3P_D0_DIN_MISO_MISO1_2-PadP10)") (class "Default")
      (node (ref "U1") (pin "P10") (pinfunction "IO_L3P_D0_DIN_MISO_MISO1_2_P10") (pintype "bidirectional"))
    )
    (net (code "148") (name "unconnected-(U1C-IO_L12N_D2_MISO3_2-PadP12)") (class "Default")
      (node (ref "U1") (pin "P12") (pinfunction "IO_L12N_D2_MISO3_2_P12") (pintype "bidirectional"))
    )
    (net (code "149") (name "unconnected-(U1C-IO_L12P_D1_MISO2_2-PadN12)") (class "Default")
      (node (ref "U1") (pin "N12") (pinfunction "IO_L12P_D1_MISO2_2_N12") (pintype "bidirectional"))
    )
    (net (code "150") (name "unconnected-(U1C-IO_L13N_D10_2-PadP11)") (class "Default")
      (node (ref "U1") (pin "P11") (pinfunction "IO_L13N_D10_2_P11") (pintype "bidirectional"))
    )
    (net (code "151") (name "unconnected-(U1C-IO_L13P_M1_2-PadN11)") (class "Default")
      (node (ref "U1") (pin "N11") (pinfunction "IO_L13P_M1_2_N11") (pintype "bidirectional"))
    )
    (net (code "152") (name "unconnected-(U1C-IO_L14N_D12_2-PadP9)") (class "Default")
      (node (ref "U1") (pin "P9") (pinfunction "IO_L14N_D12_2_P9") (pintype "bidirectional"))
    )
    (net (code "153") (name "unconnected-(U1C-IO_L14P_D11_2-PadN9)") (class "Default")
      (node (ref "U1") (pin "N9") (pinfunction "IO_L14P_D11_2_N9") (pintype "bidirectional"))
    )
    (net (code "154") (name "unconnected-(U1C-IO_L16N_VREF_2-PadM10)") (class "Default")
      (node (ref "U1") (pin "M10") (pinfunction "IO_L16N_VREF_2_M10") (pintype "bidirectional"))
    )
    (net (code "155") (name "unconnected-(U1C-IO_L16P_2-PadL10)") (class "Default")
      (node (ref "U1") (pin "L10") (pinfunction "IO_L16P_2_L10") (pintype "bidirectional"))
    )
    (net (code "156") (name "unconnected-(U1C-IO_L23N_2-PadT9)") (class "Default")
      (node (ref "U1") (pin "T9") (pinfunction "IO_L23N_2_T9") (pintype "bidirectional"))
    )
    (net (code "157") (name "unconnected-(U1C-IO_L23P_2-PadR9)") (class "Default")
      (node (ref "U1") (pin "R9") (pinfunction "IO_L23P_2_R9") (pintype "bidirectional"))
    )
    (net (code "158") (name "unconnected-(U1C-IO_L29N_GCLK2_2-PadN8)") (class "Default")
      (node (ref "U1") (pin "N8") (pinfunction "IO_L29N_GCLK2_2_N8") (pintype "bidirectional"))
    )
    (net (code "159") (name "unconnected-(U1C-IO_L29P_GCLK3_2-PadM9)") (class "Default")
      (node (ref "U1") (pin "M9") (pinfunction "IO_L29P_GCLK3_2_M9") (pintype "bidirectional"))
    )
    (net (code "160") (name "unconnected-(U1C-IO_L30N_GCLK0_USERCCLK_2-PadT8)") (class "Default")
      (node (ref "U1") (pin "T8") (pinfunction "IO_L30N_GCLK0_USERCCLK_2_T8") (pintype "bidirectional"))
    )
    (net (code "161") (name "unconnected-(U1C-IO_L30P_GCLK1_D13_2-PadP8)") (class "Default")
      (node (ref "U1") (pin "P8") (pinfunction "IO_L30P_GCLK1_D13_2_P8") (pintype "bidirectional"))
    )
    (net (code "162") (name "unconnected-(U1C-IO_L31N_GCLK30_D15_2-PadM7)") (class "Default")
      (node (ref "U1") (pin "M7") (pinfunction "IO_L31N_GCLK30_D15_2_M7") (pintype "bidirectional"))
    )
    (net (code "163") (name "unconnected-(U1C-IO_L31P_GCLK31_D14_2-PadP7)") (class "Default")
      (node (ref "U1") (pin "P7") (pinfunction "IO_L31P_GCLK31_D14_2_P7") (pintype "bidirectional"))
    )
    (net (code "164") (name "unconnected-(U1C-IO_L32P_GCLK29_2-PadR7)") (class "Default")
      (node (ref "U1") (pin "R7") (pinfunction "IO_L32P_GCLK29_2_R7") (pintype "bidirectional"))
    )
    (net (code "165") (name "unconnected-(U1C-IO_L47P_2-PadP6)") (class "Default")
      (node (ref "U1") (pin "P6") (pinfunction "IO_L47P_2_P6") (pintype "bidirectional"))
    )
    (net (code "166") (name "unconnected-(U1C-IO_L48P_D7_2-PadR5)") (class "Default")
      (node (ref "U1") (pin "R5") (pinfunction "IO_L48P_D7_2_R5") (pintype "bidirectional"))
    )
    (net (code "167") (name "unconnected-(U1C-IO_L49N_D4_2-PadP5)") (class "Default")
      (node (ref "U1") (pin "P5") (pinfunction "IO_L49N_D4_2_P5") (pintype "bidirectional"))
    )
    (net (code "168") (name "unconnected-(U1C-IO_L49P_D3_2-PadN5)") (class "Default")
      (node (ref "U1") (pin "N5") (pinfunction "IO_L49P_D3_2_N5") (pintype "bidirectional"))
    )
    (net (code "169") (name "unconnected-(U1C-IO_L62N_D6_2-PadL7)") (class "Default")
      (node (ref "U1") (pin "L7") (pinfunction "IO_L62N_D6_2_L7") (pintype "bidirectional"))
    )
    (net (code "170") (name "unconnected-(U1C-IO_L62P_D5_2-PadL8)") (class "Default")
      (node (ref "U1") (pin "L8") (pinfunction "IO_L62P_D5_2_L8") (pintype "bidirectional"))
    )
    (net (code "171") (name "unconnected-(U1C-IO_L63P_2-PadP4)") (class "Default")
      (node (ref "U1") (pin "P4") (pinfunction "IO_L63P_2_P4") (pintype "bidirectional"))
    )
    (net (code "172") (name "unconnected-(U1C-IO_L64N_D9_2-PadN6)") (class "Default")
      (node (ref "U1") (pin "N6") (pinfunction "IO_L64N_D9_2_N6") (pintype "bidirectional"))
    )
    (net (code "173") (name "unconnected-(U1C-IO_L64P_D8_2-PadM6)") (class "Default")
      (node (ref "U1") (pin "M6") (pinfunction "IO_L64P_D8_2_M6") (pintype "bidirectional"))
    )
    (net (code "174") (name "unconnected-(U1C-IO_L65N_CSO_B_2-PadT3)") (class "Default")
      (node (ref "U1") (pin "T3") (pinfunction "IO_L65N_CSO_B_2_T3") (pintype "bidirectional"))
    )
    (net (code "175") (name "unconnected-(U1C-IO_L65P_INIT_B_2-PadR3)") (class "Default")
      (node (ref "U1") (pin "R3") (pinfunction "IO_L65P_INIT_B_2_R3") (pintype "bidirectional"))
    )
    (net (code "176") (name "unconnected-(U1D-IO_L1N_VREF_3-PadM3)") (class "Default")
      (node (ref "U1") (pin "M3") (pinfunction "IO_L1N_VREF_3_M3") (pintype "bidirectional"))
    )
    (net (code "177") (name "unconnected-(U1D-IO_L1P_3-PadM4)") (class "Default")
      (node (ref "U1") (pin "M4") (pinfunction "IO_L1P_3_M4") (pintype "bidirectional"))
    )
    (net (code "178") (name "unconnected-(U1D-IO_L2N_3-PadN4)") (class "Default")
      (node (ref "U1") (pin "N4") (pinfunction "IO_L2N_3_N4") (pintype "bidirectional"))
    )
    (net (code "179") (name "unconnected-(U1D-IO_L2P_3-PadM5)") (class "Default")
      (node (ref "U1") (pin "M5") (pinfunction "IO_L2P_3_M5") (pintype "bidirectional"))
    )
    (net (code "180") (name "unconnected-(U1D-IO_L34P_M3UDQS_3-PadN3)") (class "Default")
      (node (ref "U1") (pin "N3") (pinfunction "IO_L34P_M3UDQS_3_N3") (pintype "bidirectional"))
    )
    (net (code "181") (name "unconnected-(U1D-IO_L42N_GCLK24_M3LDM_3-PadJ4)") (class "Default")
      (node (ref "U1") (pin "J4") (pinfunction "IO_L42N_GCLK24_M3LDM_3_J4") (pintype "bidirectional"))
    )
    (net (code "182") (name "unconnected-(U1D-IO_L43N_GCLK22_IRDY2_M3CASN_3-PadH5)") (class "Default")
      (node (ref "U1") (pin "H5") (pinfunction "IO_L43N_GCLK22_IRDY2_M3CASN_3_H5") (pintype "bidirectional"))
    )
    (net (code "183") (name "unconnected-(U1D-IO_L43P_GCLK23_M3RASN_3-PadJ6)") (class "Default")
      (node (ref "U1") (pin "J6") (pinfunction "IO_L43P_GCLK23_M3RASN_3_J6") (pintype "bidirectional"))
    )
    (net (code "184") (name "unconnected-(U1D-IO_L44P_GCLK21_M3A5_3-PadH4)") (class "Default")
      (node (ref "U1") (pin "H4") (pinfunction "IO_L44P_GCLK21_M3A5_3_H4") (pintype "bidirectional"))
    )
    (net (code "185") (name "unconnected-(U1D-IO_L45N_M3ODT_3-PadL5)") (class "Default")
      (node (ref "U1") (pin "L5") (pinfunction "IO_L45N_M3ODT_3_L5") (pintype "bidirectional"))
    )
    (net (code "186") (name "unconnected-(U1D-IO_L45P_M3A3_3-PadL4)") (class "Default")
      (node (ref "U1") (pin "L4") (pinfunction "IO_L45P_M3A3_3_L4") (pintype "bidirectional"))
    )
    (net (code "187") (name "unconnected-(U1D-IO_L47N_M3A1_3-PadK6)") (class "Default")
      (node (ref "U1") (pin "K6") (pinfunction "IO_L47N_M3A1_3_K6") (pintype "bidirectional"))
    )
    (net (code "188") (name "unconnected-(U1D-IO_L47P_M3A0_3-PadK5)") (class "Default")
      (node (ref "U1") (pin "K5") (pinfunction "IO_L47P_M3A0_3_K5") (pintype "bidirectional"))
    )
    (net (code "189") (name "unconnected-(U1D-IO_L51N_M3A4_3-PadG5)") (class "Default")
      (node (ref "U1") (pin "G5") (pinfunction "IO_L51N_M3A4_3_G5") (pintype "bidirectional"))
    )
    (net (code "190") (name "unconnected-(U1D-IO_L51P_M3A10_3-PadG6)") (class "Default")
      (node (ref "U1") (pin "G6") (pinfunction "IO_L51P_M3A10_3_G6") (pintype "bidirectional"))
    )
    (net (code "191") (name "unconnected-(U1D-IO_L53P_M3CKE_3-PadF4)") (class "Default")
      (node (ref "U1") (pin "F4") (pinfunction "IO_L53P_M3CKE_3_F4") (pintype "bidirectional"))
    )
    (net (code "192") (name "unconnected-(U1D-IO_L55N_M3A14_3-PadF5)") (class "Default")
      (node (ref "U1") (pin "F5") (pinfunction "IO_L55N_M3A14_3_F5") (pintype "bidirectional"))
    )
    (net (code "193") (name "unconnected-(U1D-IO_L55P_M3A13_3-PadF6)") (class "Default")
      (node (ref "U1") (pin "F6") (pinfunction "IO_L55P_M3A13_3_F6") (pintype "bidirectional"))
    )
    (net (code "194") (name "unconnected-(U1E-CMPCS_B_2-PadL11)") (class "Default")
      (node (ref "U1") (pin "L11") (pinfunction "CMPCS_B_2_L11") (pintype "input"))
    )
    (net (code "195") (name "unconnected-(U1E-DONE_2-PadP13)") (class "Default")
      (node (ref "U1") (pin "P13") (pinfunction "DONE_2_P13") (pintype "bidirectional"))
    )
    (net (code "196") (name "unconnected-(U1E-PROGRAM_B_2-PadT2)") (class "Default")
      (node (ref "U1") (pin "T2") (pinfunction "PROGRAM_B_2_T2") (pintype "input"))
    )
    (net (code "197") (name "unconnected-(U1E-SUSPEND-PadP14)") (class "Default")
      (node (ref "U1") (pin "P14") (pinfunction "SUSPEND_P14") (pintype "input"))
    )
  )
)
